# VARIOS.net
KiCad netlist of a schematic drawn in Altium Designer
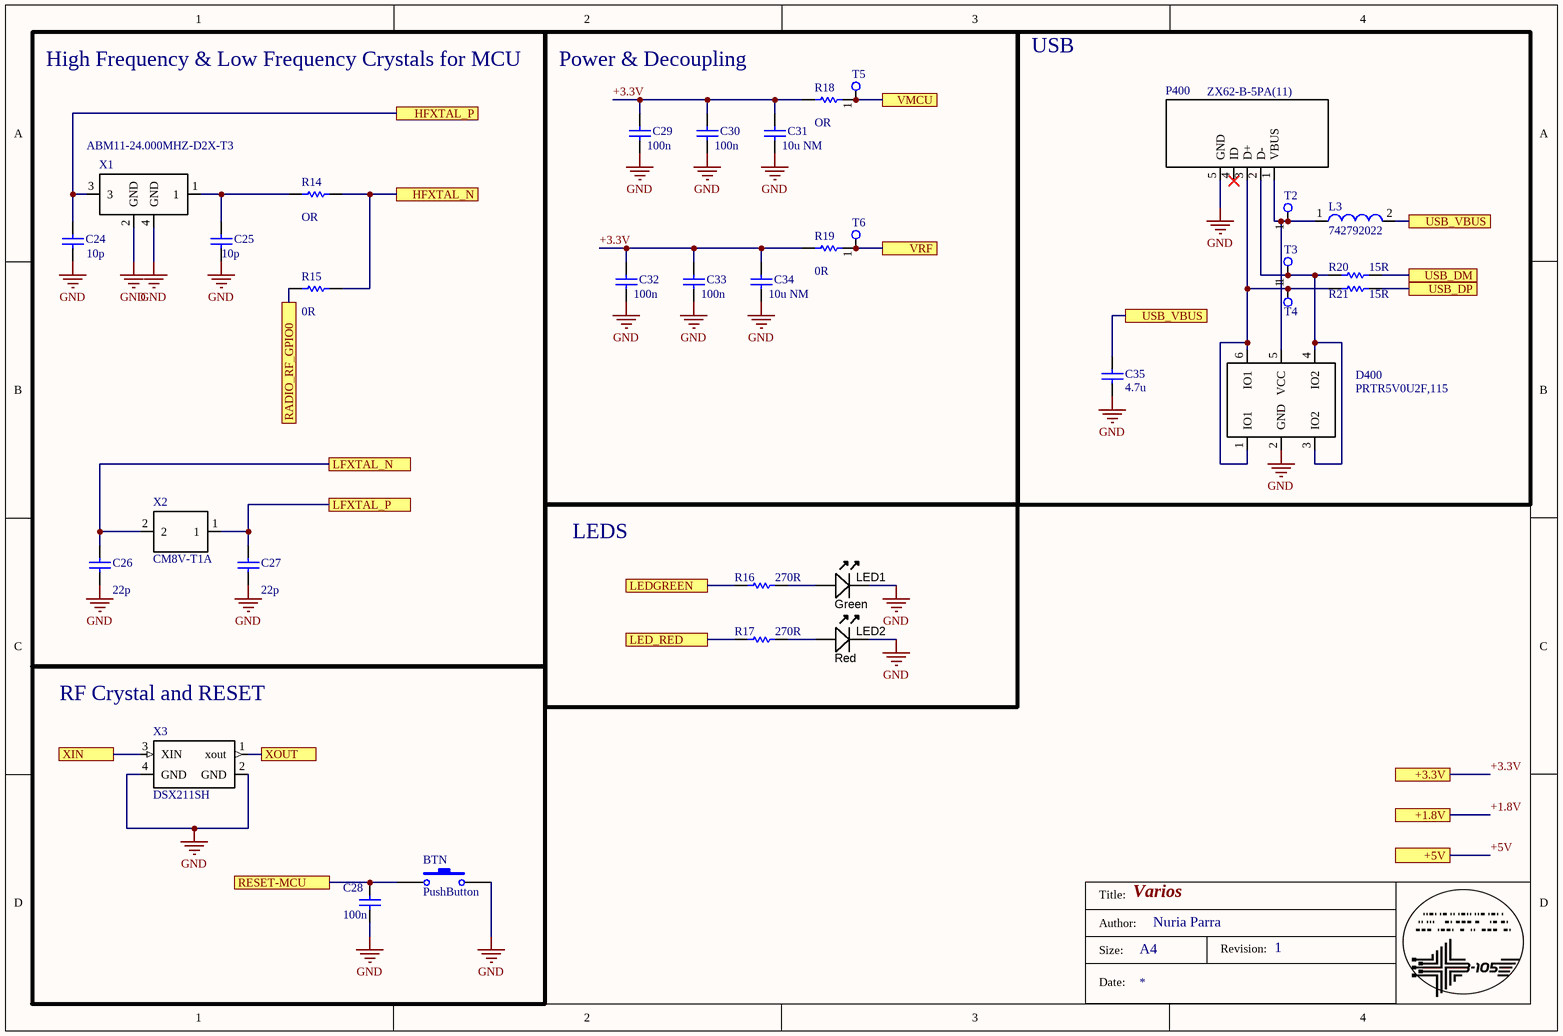
[diagram p0: VARIOS.SchDoc]

(export (version "E")
  (design (tool "Eeschema 10.0.6"))
  (components
    (comp (ref "BTN")
      (value "PushButton")
      (footprint "Push button SMD 2 leads")
      (libsource (lib "B105connectors") (part "PushButton"))
    )
    (comp (ref "C24")
      (value "10p")
      (footprint "0603 Cap")
      (fields (field (name "Comment") "Cap"))
      (libsource (lib "B105rlc") (part "Cap"))
    )
    (comp (ref "C25")
      (value "10p")
      (footprint "0603 Cap")
      (fields (field (name "Comment") "Cap"))
      (libsource (lib "B105rlc") (part "Cap"))
    )
    (comp (ref "C26")
      (value "22p")
      (footprint "0603 Cap")
      (fields (field (name "Comment") "Cap"))
      (libsource (lib "B105rlc") (part "Cap"))
    )
    (comp (ref "C27")
      (value "22p")
      (footprint "0603 Cap")
      (fields (field (name "Comment") "Cap"))
      (libsource (lib "B105rlc") (part "Cap"))
    )
    (comp (ref "C28")
      (value "100n")
      (footprint "0603 Cap")
      (fields (field (name "Comment") "Cap"))
      (libsource (lib "B105rlc") (part "Cap"))
    )
    (comp (ref "C29")
      (value "100n")
      (footprint "0603 Cap")
      (fields (field (name "Comment") "Cap"))
      (libsource (lib "B105rlc") (part "Cap"))
    )
    (comp (ref "C30")
      (value "100n")
      (footprint "0603 Cap")
      (fields (field (name "Comment") "Cap"))
      (libsource (lib "B105rlc") (part "Cap"))
    )
    (comp (ref "C31")
      (value "10u NM")
      (footprint "0603 Cap")
      (fields (field (name "Comment") "Cap"))
      (libsource (lib "B105rlc") (part "Cap"))
    )
    (comp (ref "C32")
      (value "100n")
      (footprint "0603 Cap")
      (fields (field (name "Comment") "Cap"))
      (libsource (lib "B105rlc") (part "Cap"))
    )
    (comp (ref "C33")
      (value "100n")
      (footprint "0603 Cap")
      (fields (field (name "Comment") "Cap"))
      (libsource (lib "B105rlc") (part "Cap"))
    )
    (comp (ref "C34")
      (value "10u NM")
      (footprint "0603 Cap")
      (fields (field (name "Comment") "Cap"))
      (libsource (lib "B105rlc") (part "Cap"))
    )
    (comp (ref "C35")
      (value "4.7u")
      (footprint "0603 Cap")
      (fields (field (name "Comment") "Cap"))
      (libsource (lib "B105rlc") (part "Cap"))
    )
    (comp (ref "D400")
      (value "PRTR5V0U2F,115")
      (footprint "PRTR5V0U2F,115")
      (libsource (lib "Libreria Nuria") (part "PRTR5V0U2F,115"))
    )
    (comp (ref "L3")
      (value "742792022")
      (footprint "ferritel3")
      (libsource (lib "Libreria Nuria") (part "742792022"))
    )
    (comp (ref "LED1")
      (value "Green")
      (footprint "LED-0603-RED")
      (description "LED 0603 SMD Green 570nm 50mcd 20mA")
      (libsource (lib "PBL - Light Sources") (part "LED_SMD_Green_0603_570nm"))
    )
    (comp (ref "LED2")
      (value "Red")
      (footprint "LED-0603-RED")
      (description "LED 0603 SMD Hyper Red 630nm 220mcd 20mA")
      (libsource (lib "PBL - Light Sources") (part "LED_SMD_Red_0603_220mcd"))
    )
    (comp (ref "P400")
      (value "ZX62-B-5PA(11)")
      (footprint "ZX62-B-5PA(11)")
      (libsource (lib "Libreria Nuria") (part "ZX62-B-5PA(11)"))
    )
    (comp (ref "R14")
      (value "OR")
      (footprint "0603 Res")
      (fields (field (name "Comment") "Res"))
      (libsource (lib "B105rlc") (part "Res"))
    )
    (comp (ref "R15")
      (value "0R")
      (footprint "0603 Res")
      (fields (field (name "Comment") "Res"))
      (libsource (lib "B105rlc") (part "Res"))
    )
    (comp (ref "R16")
      (value "270R")
      (footprint "0603 Res")
      (fields (field (name "Comment") "Res"))
      (libsource (lib "B105rlc") (part "Res"))
    )
    (comp (ref "R17")
      (value "270R")
      (footprint "0603 Res")
      (fields (field (name "Comment") "Res"))
      (libsource (lib "B105rlc") (part "Res"))
    )
    (comp (ref "R18")
      (value "OR")
      (footprint "0603 Res")
      (fields (field (name "Comment") "Res"))
      (libsource (lib "B105rlc") (part "Res"))
    )
    (comp (ref "R19")
      (value "0R")
      (footprint "0603 Res")
      (fields (field (name "Comment") "Res"))
      (libsource (lib "B105rlc") (part "Res"))
    )
    (comp (ref "R20")
      (value "15R")
      (footprint "0603 Res")
      (fields (field (name "Comment") "Res"))
      (libsource (lib "B105rlc") (part "Res"))
    )
    (comp (ref "R21")
      (value "15R")
      (footprint "0603 Res")
      (fields (field (name "Comment") "Res"))
      (libsource (lib "B105rlc") (part "Res"))
    )
    (comp (ref "T2")
      (value "testpoint")
      (footprint "testpoint")
      (libsource (lib "Libreria Nuria") (part "testpoint"))
    )
    (comp (ref "T3")
      (value "testpoint")
      (footprint "testpoint")
      (libsource (lib "Libreria Nuria") (part "testpoint"))
    )
    (comp (ref "T4")
      (value "testpoint")
      (footprint "testpoint")
      (libsource (lib "Libreria Nuria") (part "testpoint"))
    )
    (comp (ref "T5")
      (value "testpoint")
      (footprint "testpoint")
      (libsource (lib "Libreria Nuria") (part "testpoint"))
    )
    (comp (ref "T6")
      (value "testpoint")
      (footprint "testpoint")
      (libsource (lib "Libreria Nuria") (part "testpoint"))
    )
    (comp (ref "X1")
      (value "ABM11-24.000MHZ-D2X-T3")
      (footprint "abm")
      (libsource (lib "Libreria Nuria") (part "ABM11-24.000MHZ-D2X-T3"))
    )
    (comp (ref "X2")
      (value "CM8V-T1A")
      (footprint "CM8V-T1A")
      (libsource (lib "Libreria Nuria") (part "CM8V-T1A"))
    )
    (comp (ref "X3")
      (value "DSX211SH")
      (footprint "DSX211SH")
      (libsource (lib "Libreria Nuria") (part "DSX211SH"))
    )
  )
  (nets
    (net (code "2") (name "/+3.3V") (class "Default")
      (node (ref "C29") (pin "2") (pinfunction "2_2") (pintype "passive"))
      (node (ref "C30") (pin "2") (pinfunction "2_2") (pintype "passive"))
      (node (ref "C31") (pin "2") (pinfunction "2_2") (pintype "passive"))
      (node (ref "C32") (pin "2") (pinfunction "2_2") (pintype "passive"))
      (node (ref "C33") (pin "2") (pinfunction "2_2") (pintype "passive"))
      (node (ref "C34") (pin "2") (pinfunction "2_2") (pintype "passive"))
      (node (ref "R18") (pin "1") (pinfunction "1_1") (pintype "passive"))
      (node (ref "R19") (pin "1") (pinfunction "1_1") (pintype "passive"))
    )
    (net (code "4") (name "/HFXTAL_N") (class "Default")
      (node (ref "R14") (pin "2") (pinfunction "2_2") (pintype "passive"))
      (node (ref "R15") (pin "2") (pinfunction "2_2") (pintype "passive"))
    )
    (net (code "5") (name "/HFXTAL_P") (class "Default")
      (node (ref "C24") (pin "2") (pinfunction "2_2") (pintype "passive"))
      (node (ref "X1") (pin "3") (pinfunction "3_3") (pintype "passive"))
    )
    (net (code "6") (name "/LEDGREEN") (class "Default")
      (node (ref "R16") (pin "2") (pinfunction "2_2") (pintype "passive"))
    )
    (net (code "7") (name "/LED_RED") (class "Default")
      (node (ref "R17") (pin "2") (pinfunction "2_2") (pintype "passive"))
    )
    (net (code "8") (name "/LFXTAL_N") (class "Default")
      (node (ref "C26") (pin "2") (pinfunction "2_2") (pintype "passive"))
      (node (ref "X2") (pin "2") (pinfunction "2_2") (pintype "passive"))
    )
    (net (code "9") (name "/LFXTAL_P") (class "Default")
      (node (ref "C27") (pin "2") (pinfunction "2_2") (pintype "passive"))
      (node (ref "X2") (pin "1") (pinfunction "1_1") (pintype "passive"))
    )
    (net (code "10") (name "/RADIO_RF_GPIO0") (class "Default")
      (node (ref "R15") (pin "1") (pinfunction "1_1") (pintype "passive"))
    )
    (net (code "11") (name "/RESET-MCU") (class "Default")
      (node (ref "BTN") (pin "1") (pinfunction "1_1") (pintype "passive"))
      (node (ref "C28") (pin "2") (pinfunction "2_2") (pintype "passive"))
    )
    (net (code "12") (name "/USB_DM") (class "Default")
      (node (ref "R20") (pin "1") (pinfunction "1_1") (pintype "passive"))
    )
    (net (code "13") (name "/USB_DP") (class "Default")
      (node (ref "R21") (pin "1") (pinfunction "1_1") (pintype "passive"))
    )
    (net (code "14") (name "/USB_VBUS") (class "Default")
      (node (ref "C35") (pin "1") (pinfunction "1_1") (pintype "passive"))
      (node (ref "L3") (pin "2") (pinfunction "2_2") (pintype "passive"))
    )
    (net (code "15") (name "/VMCU") (class "Default")
      (node (ref "R18") (pin "2") (pinfunction "2_2") (pintype "passive"))
      (node (ref "T5") (pin "1") (pinfunction "TP_1") (pintype "passive"))
    )
    (net (code "16") (name "/VRF") (class "Default")
      (node (ref "R19") (pin "2") (pinfunction "2_2") (pintype "passive"))
      (node (ref "T6") (pin "1") (pinfunction "TP_1") (pintype "passive"))
    )
    (net (code "17") (name "/XIN") (class "Default")
      (node (ref "X3") (pin "3") (pinfunction "XIN_3") (pintype "input"))
    )
    (net (code "18") (name "/XOUT") (class "Default")
      (node (ref "X3") (pin "1") (pinfunction "xout_1") (pintype "output"))
    )
    (net (code "19") (name "GND") (class "Default")
      (node (ref "BTN") (pin "2") (pinfunction "2_2") (pintype "passive"))
      (node (ref "C24") (pin "1") (pinfunction "1_1") (pintype "passive"))
      (node (ref "C25") (pin "1") (pinfunction "1_1") (pintype "passive"))
      (node (ref "C26") (pin "1") (pinfunction "1_1") (pintype "passive"))
      (node (ref "C27") (pin "1") (pinfunction "1_1") (pintype "passive"))
      (node (ref "C28") (pin "1") (pinfunction "1_1") (pintype "passive"))
      (node (ref "C29") (pin "1") (pinfunction "1_1") (pintype "passive"))
      (node (ref "C30") (pin "1") (pinfunction "1_1") (pintype "passive"))
      (node (ref "C31") (pin "1") (pinfunction "1_1") (pintype "passive"))
      (node (ref "C32") (pin "1") (pinfunction "1_1") (pintype "passive"))
      (node (ref "C33") (pin "1") (pinfunction "1_1") (pintype "passive"))
      (node (ref "C34") (pin "1") (pinfunction "1_1") (pintype "passive"))
      (node (ref "C35") (pin "2") (pinfunction "2_2") (pintype "passive"))
      (node (ref "D400") (pin "2") (pinfunction "GND_2") (pintype "power_in"))
      (node (ref "LED1") (pin "K") (pinfunction "K_K") (pintype "passive"))
      (node (ref "LED2") (pin "K") (pinfunction "K_K") (pintype "passive"))
      (node (ref "P400") (pin "5") (pinfunction "GND_5") (pintype "power_in"))
      (node (ref "X1") (pin "2") (pinfunction "GND_2") (pintype "power_in"))
      (node (ref "X1") (pin "4") (pinfunction "GND_4") (pintype "power_in"))
      (node (ref "X3") (pin "2") (pinfunction "GND_2") (pintype "power_in"))
      (node (ref "X3") (pin "4") (pinfunction "GND_4") (pintype "power_in"))
    )
    (net (code "20") (name "Net-(C25-Pad2)") (class "Default")
      (node (ref "C25") (pin "2") (pinfunction "2_2") (pintype "passive"))
      (node (ref "R14") (pin "1") (pinfunction "1_1") (pintype "passive"))
      (node (ref "X1") (pin "1") (pinfunction "1_1") (pintype "passive"))
    )
    (net (code "21") (name "Net-(D400-VCC)") (class "Default")
      (node (ref "D400") (pin "5") (pinfunction "VCC_5") (pintype "power_in"))
      (node (ref "L3") (pin "1") (pinfunction "1_1") (pintype "passive"))
      (node (ref "P400") (pin "1") (pinfunction "VBUS_1") (pintype "power_in"))
      (node (ref "T2") (pin "1") (pinfunction "TP_1") (pintype "passive"))
    )
    (net (code "22") (name "Net-(LED1-PadA)") (class "Default")
      (node (ref "LED1") (pin "A") (pinfunction "A_A") (pintype "passive"))
      (node (ref "R16") (pin "1") (pinfunction "1_1") (pintype "passive"))
    )
    (net (code "23") (name "Net-(LED2-PadA)") (class "Default")
      (node (ref "LED2") (pin "A") (pinfunction "A_A") (pintype "passive"))
      (node (ref "R17") (pin "1") (pinfunction "1_1") (pintype "passive"))
    )
    (net (code "24") (name "Net-(P400-D+)") (class "Default")
      (node (ref "D400") (pin "1") (pinfunction "IO1_1") (pintype "bidirectional"))
      (node (ref "D400") (pin "6") (pinfunction "IO1_6") (pintype "bidirectional"))
      (node (ref "P400") (pin "3") (pinfunction "D+_3") (pintype "bidirectional"))
      (node (ref "R21") (pin "2") (pinfunction "2_2") (pintype "passive"))
      (node (ref "T4") (pin "1") (pinfunction "TP_1") (pintype "passive"))
    )
    (net (code "25") (name "Net-(P400-D-)") (class "Default")
      (node (ref "D400") (pin "3") (pinfunction "IO2_3") (pintype "bidirectional"))
      (node (ref "D400") (pin "4") (pinfunction "IO2_4") (pintype "bidirectional"))
      (node (ref "P400") (pin "2") (pinfunction "D-_2") (pintype "bidirectional"))
      (node (ref "R20") (pin "2") (pinfunction "2_2") (pintype "passive"))
      (node (ref "T3") (pin "1") (pinfunction "TP_1") (pintype "passive"))
    )
    (net (code "26") (name "unconnected-(P400-ID-Pad4)") (class "Default")
      (node (ref "P400") (pin "4") (pinfunction "ID_4") (pintype "bidirectional+no_connect"))
    )
  )
)
